# 17-INTERFACE.net
KiCad netlist of a schematic drawn in Altium Designer
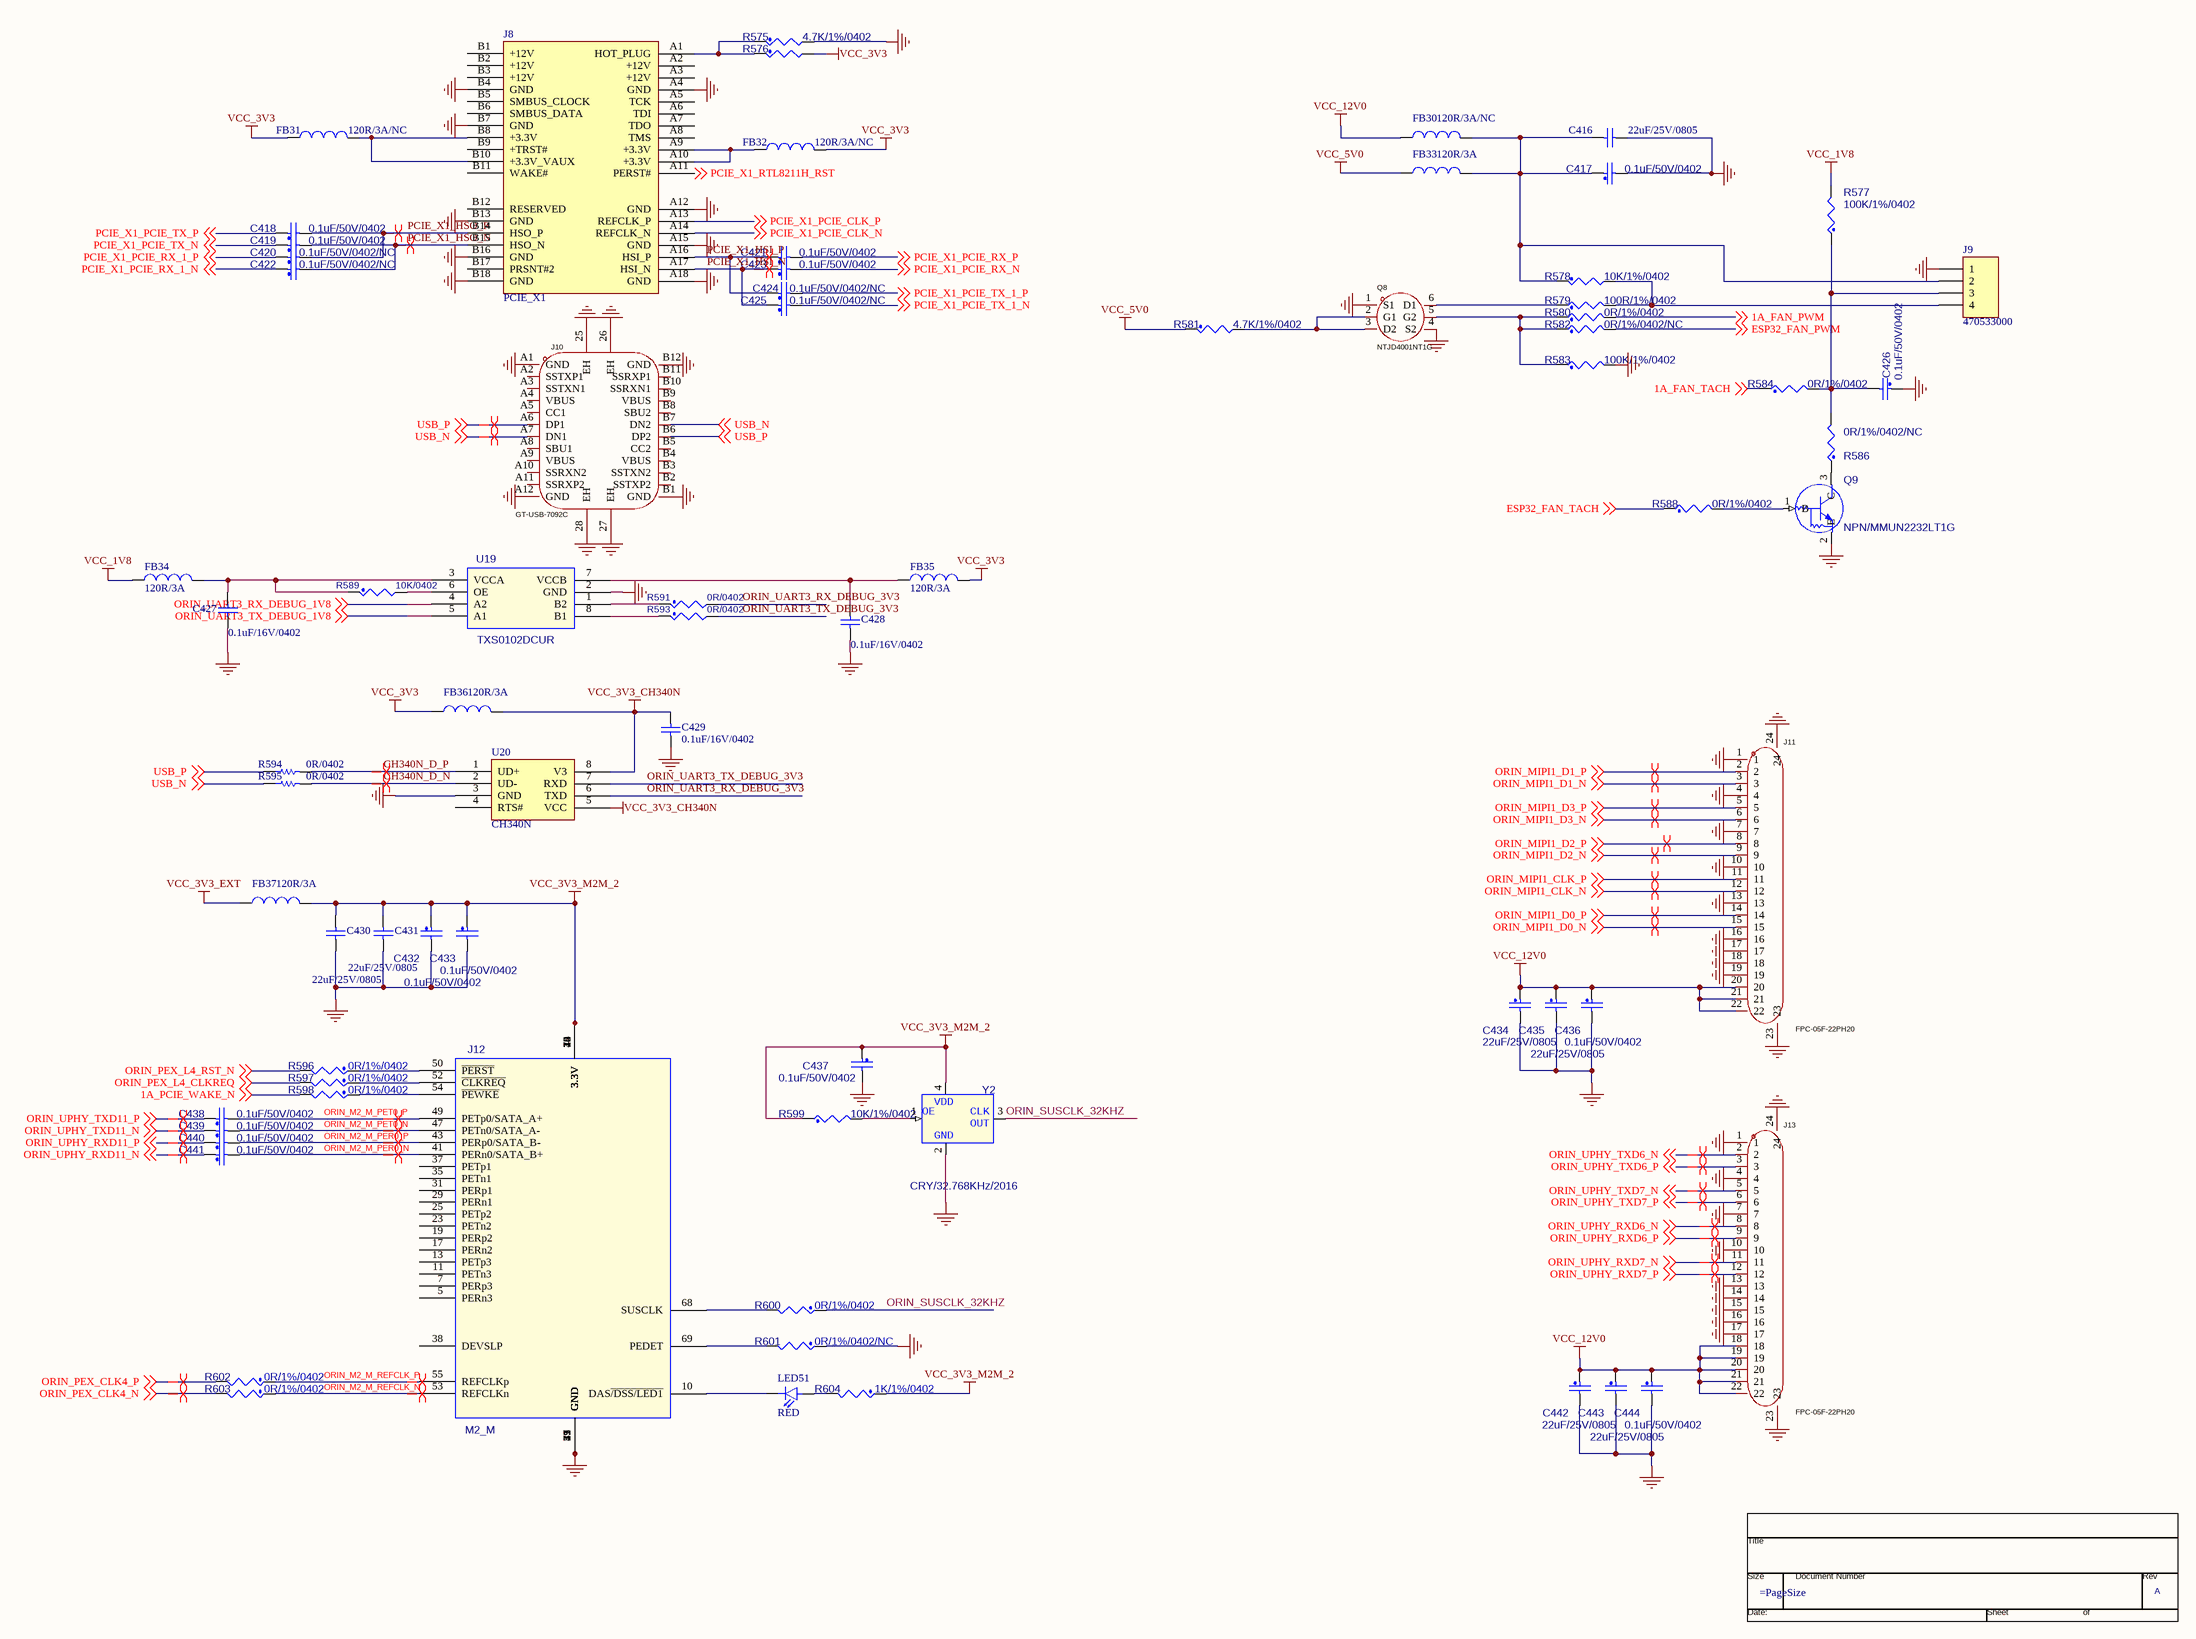
[diagram p0: 17-INTERFACE.SchDoc]

(export (version "E")
  (design (tool "Eeschema 10.0.6"))
  (components
    (comp (ref "C416")
      (value "22uF/25V/0805")
      (description "Capacitor")
      (fields (field (name "PUBLISHER") "Altium Limited"))
      (libsource (lib "LIBS") (part "CAP"))
    )
    (comp (ref "C417")
      (value "0.1uF/50V/0402")
      (footprint "C0402")
      (description "GCM155R71H104KE02/MURATA")
      (fields (field (name "TOLERANCE") "10%") (field (name "VOLTAGE") "16V"))
      (libsource (lib "*") (part "CAP_NP"))
    )
    (comp (ref "C418")
      (value "0.1uF/50V/0402")
      (footprint "C0402")
      (description "GCM155R71H104KE02/MURATA")
      (fields (field (name "TOLERANCE") "10%") (field (name "VOLTAGE") "16V"))
      (libsource (lib "*") (part "CAP_NP"))
    )
    (comp (ref "C419")
      (value "0.1uF/50V/0402")
      (footprint "C0402")
      (description "GCM155R71H104KE02/MURATA")
      (fields (field (name "TOLERANCE") "10%") (field (name "VOLTAGE") "16V"))
      (libsource (lib "*") (part "CAP_NP"))
    )
    (comp (ref "C420")
      (value "0.1uF/50V/0402/NC")
      (footprint "C0402")
      (description "GCM155R71H104KE02/MURATA")
      (fields (field (name "TOLERANCE") "10%") (field (name "VOLTAGE") "16V"))
      (libsource (lib "*") (part "CAP_NP"))
    )
    (comp (ref "C421")
      (value "0.1uF/50V/0402")
      (footprint "C0402")
      (description "GCM155R71H104KE02/MURATA")
      (fields (field (name "TOLERANCE") "10%") (field (name "VOLTAGE") "16V"))
      (libsource (lib "*") (part "CAP_NP"))
    )
    (comp (ref "C422")
      (value "0.1uF/50V/0402/NC")
      (footprint "C0402")
      (description "GCM155R71H104KE02/MURATA")
      (fields (field (name "TOLERANCE") "10%") (field (name "VOLTAGE") "16V"))
      (libsource (lib "*") (part "CAP_NP"))
    )
    (comp (ref "C423")
      (value "0.1uF/50V/0402")
      (footprint "C0402")
      (description "GCM155R71H104KE02/MURATA")
      (fields (field (name "TOLERANCE") "10%") (field (name "VOLTAGE") "16V"))
      (libsource (lib "*") (part "CAP_NP"))
    )
    (comp (ref "C424")
      (value "0.1uF/50V/0402/NC")
      (footprint "C0402")
      (description "GCM155R71H104KE02/MURATA")
      (fields (field (name "TOLERANCE") "10%") (field (name "VOLTAGE") "16V"))
      (libsource (lib "*") (part "CAP_NP"))
    )
    (comp (ref "C425")
      (value "0.1uF/50V/0402/NC")
      (footprint "C0402")
      (description "GCM155R71H104KE02/MURATA")
      (fields (field (name "TOLERANCE") "10%") (field (name "VOLTAGE") "16V"))
      (libsource (lib "*") (part "CAP_NP"))
    )
    (comp (ref "C426")
      (value "0.1uF/50V/0402")
      (footprint "C0402")
      (description "GCM155R71H104KE02/MURATA")
      (fields (field (name "TOLERANCE") "10%") (field (name "VOLTAGE") "16V"))
      (libsource (lib "*") (part "CAP_NP"))
    )
    (comp (ref "C427")
      (value "0.1uF/16V/0402")
      (description "Capacitor")
      (fields (field (name "PUBLISHER") "Altium Limited"))
      (libsource (lib "LIBS") (part "CAP"))
    )
    (comp (ref "C428")
      (value "0.1uF/16V/0402")
      (description "Capacitor")
      (fields (field (name "PUBLISHER") "Altium Limited"))
      (libsource (lib "LIBS") (part "CAP"))
    )
    (comp (ref "C429")
      (value "0.1uF/16V/0402")
      (description "Capacitor")
      (fields (field (name "PUBLISHER") "Altium Limited"))
      (libsource (lib "LIBS") (part "CAP"))
    )
    (comp (ref "C430")
      (value "22uF/25V/0805")
      (description "Capacitor")
      (fields (field (name "PUBLISHER") "Altium Limited"))
      (libsource (lib "LIBS") (part "CAP"))
    )
    (comp (ref "C431")
      (value "22uF/25V/0805")
      (description "Capacitor")
      (fields (field (name "PUBLISHER") "Altium Limited"))
      (libsource (lib "LIBS") (part "CAP"))
    )
    (comp (ref "C432")
      (value "0.1uF/50V/0402")
      (footprint "C0402")
      (description "GCM155R71H104KE02/MURATA")
      (fields (field (name "TOLERANCE") "10%") (field (name "VOLTAGE") "16V"))
      (libsource (lib "*") (part "CAP_NP"))
    )
    (comp (ref "C433")
      (value "0.1uF/50V/0402")
      (footprint "C0402")
      (description "GCM155R71H104KE02/MURATA")
      (fields (field (name "TOLERANCE") "10%") (field (name "VOLTAGE") "16V"))
      (libsource (lib "*") (part "CAP_NP"))
    )
    (comp (ref "C434")
      (value "22uF/25V/0805")
      (footprint "C0805")
      (description "GRT31CC71E226ME13/MURATA")
      (fields (field (name "VOLTAGE") "10v") (field (name "TOLERANCE") "10%"))
      (libsource (lib "*") (part "CAP_NP"))
    )
    (comp (ref "C435")
      (value "22uF/25V/0805")
      (footprint "C0805")
      (description "GRT31CC71E226ME13/MURATA")
      (fields (field (name "VOLTAGE") "10v") (field (name "TOLERANCE") "10%"))
      (libsource (lib "*") (part "CAP_NP"))
    )
    (comp (ref "C436")
      (value "0.1uF/50V/0402")
      (footprint "C0402")
      (description "GCM155R71H104KE02/MURATA")
      (fields (field (name "TOLERANCE") "10%") (field (name "VOLTAGE") "16V"))
      (libsource (lib "*") (part "CAP_NP"))
    )
    (comp (ref "C437")
      (value "0.1uF/50V/0402")
      (footprint "C0402")
      (description "GCM155R71H104KE02/MURATA")
      (libsource (lib "*") (part "CAP_NP_Dup1"))
    )
    (comp (ref "C438")
      (value "0.1uF/50V/0402")
      (footprint "C0402")
      (description "GCM155R71H104KE02/MURATA")
      (fields (field (name "TOLERANCE") "10%") (field (name "VOLTAGE") "16V"))
      (libsource (lib "*") (part "CAP_NP"))
    )
    (comp (ref "C439")
      (value "0.1uF/50V/0402")
      (footprint "C0402")
      (description "GCM155R71H104KE02/MURATA")
      (fields (field (name "TOLERANCE") "10%") (field (name "VOLTAGE") "16V"))
      (libsource (lib "*") (part "CAP_NP"))
    )
    (comp (ref "C440")
      (value "0.1uF/50V/0402")
      (footprint "C0402")
      (description "GCM155R71H104KE02/MURATA")
      (fields (field (name "TOLERANCE") "10%") (field (name "VOLTAGE") "16V"))
      (libsource (lib "*") (part "CAP_NP"))
    )
    (comp (ref "C441")
      (value "0.1uF/50V/0402")
      (footprint "C0402")
      (description "GCM155R71H104KE02/MURATA")
      (fields (field (name "TOLERANCE") "10%") (field (name "VOLTAGE") "16V"))
      (libsource (lib "*") (part "CAP_NP"))
    )
    (comp (ref "C442")
      (value "22uF/25V/0805")
      (footprint "C0805")
      (description "GRT31CC71E226ME13/MURATA")
      (fields (field (name "VOLTAGE") "10v") (field (name "TOLERANCE") "10%"))
      (libsource (lib "*") (part "CAP_NP"))
    )
    (comp (ref "C443")
      (value "22uF/25V/0805")
      (footprint "C0805")
      (description "GRT31CC71E226ME13/MURATA")
      (fields (field (name "VOLTAGE") "10v") (field (name "TOLERANCE") "10%"))
      (libsource (lib "*") (part "CAP_NP"))
    )
    (comp (ref "C444")
      (value "0.1uF/50V/0402")
      (footprint "C0402")
      (description "GCM155R71H104KE02/MURATA")
      (fields (field (name "TOLERANCE") "10%") (field (name "VOLTAGE") "16V"))
      (libsource (lib "*") (part "CAP_NP"))
    )
    (comp (ref "FB30")
      (value "120R/3A/NC")
      (footprint "L0603")
      (description "BLM18KG121TN1D")
      (fields (field (name "PUBLISHER") "Altium Limited"))
      (libsource (lib "LIBS") (part "Inductor"))
    )
    (comp (ref "FB31")
      (value "120R/3A/NC")
      (footprint "L0603")
      (description "BLM18KG121TN1D")
      (fields (field (name "PUBLISHER") "Altium Limited"))
      (libsource (lib "LIBS") (part "Inductor"))
    )
    (comp (ref "FB32")
      (value "120R/3A/NC")
      (footprint "L0603")
      (description "BLM18KG121TN1D")
      (fields (field (name "PUBLISHER") "Altium Limited"))
      (libsource (lib "LIBS") (part "Inductor"))
    )
    (comp (ref "FB33")
      (value "120R/3A")
      (footprint "L0603")
      (description "BLM18KG121TN1D")
      (fields (field (name "PUBLISHER") "Altium Limited"))
      (libsource (lib "LIBS") (part "Inductor"))
    )
    (comp (ref "FB34")
      (value "120R/3A")
      (footprint "L0603")
      (description "BLM18KG121TN1D")
      (fields (field (name "PUBLISHER") "Altium Limited"))
      (libsource (lib "LIBS") (part "Inductor"))
    )
    (comp (ref "FB35")
      (value "120R/3A")
      (footprint "L0603")
      (description "BLM18KG121TN1D")
      (fields (field (name "PUBLISHER") "Altium Limited"))
      (libsource (lib "LIBS") (part "Inductor"))
    )
    (comp (ref "FB36")
      (value "120R/3A")
      (footprint "L0603")
      (description "BLM18KG121TN1D")
      (fields (field (name "PUBLISHER") "Altium Limited"))
      (libsource (lib "LIBS") (part "Inductor"))
    )
    (comp (ref "FB37")
      (value "120R/3A")
      (footprint "L0603")
      (description "BLM18KG121TN1D")
      (fields (field (name "PUBLISHER") "Altium Limited"))
      (libsource (lib "LIBS") (part "Inductor"))
    )
    (comp (ref "J8")
      (value "PCIE_X1")
      (footprint "PCIeX16-GF-2D-1000-1K-O36")
      (libsource (lib "LIBS") (part "PCIE_X1"))
    )
    (comp (ref "J9")
      (value "470533000")
      (footprint "470533000")
      (description "Header, 4-Pin")
      (fields (field (name "PUBLISHER") "Altium Limited"))
      (libsource (lib "LIBS") (part "Header 4"))
    )
    (comp (ref "J10")
      (value "GT-USB-7092C")
      (footprint "USB-C-SMD_GT-USB-7092C")
      (fields (field (name "MANUFACTURER") "G-Switch(品赞)"))
      (libsource (lib "altium-import") (part "root_0_GT-USB-7092C_"))
    )
    (comp (ref "J11")
      (value "FPC-05F-22PH20")
      (footprint "FPC-SMD_22P-P0.50_FPC-05F-22PH20")
      (fields (field (name "MANUFACTURER") "XUNPU(讯普)"))
      (libsource (lib "altium-import") (part "root_0_FPC-05F-22PH20_"))
    )
    (comp (ref "J12")
      (value "M2_M")
      (footprint "PCIe_M.2_Connectors_P=0.5mm_H=4.2mm_KeyM - 1")
      (libsource (lib "LIBS") (part "M2_M"))
    )
    (comp (ref "J13")
      (value "FPC-05F-22PH20")
      (footprint "FPC-SMD_22P-P0.50_FPC-05F-22PH20")
      (fields (field (name "MANUFACTURER") "XUNPU(讯普)"))
      (libsource (lib "altium-import") (part "root_0_FPC-05F-22PH20_"))
    )
    (comp (ref "LED51") (value "RED") (footprint "LED0603") (libsource (lib "LIBS") (part "LED")))
    (comp (ref "Q8")
      (value "NTJD4001NT1G")
      (footprint "SOT-363_L2.0-W1.3-P0.65-LS2.1-TL")
      (fields (field (name "MANUFACTURER") "onsemi(安森美)"))
      (libsource (lib "altium-import") (part "root_0_NTJD4001NT1G_"))
    )
    (comp (ref "Q9")
      (value "NPN/MMUN2232LT1G")
      (footprint "SOT-23")
      (description "MMUN2232LT1G/ONSEMI")
      (libsource (lib "*") (part "DTC143ZE"))
    )
    (comp (ref "R575")
      (value "4.7K/1%/0402")
      (footprint "R0402")
      (description "AC0402FR-074K7L/YAGEO")
      (fields (field (name "TOLERANCE") "5%") (field (name "Comment") "RES_Dup2"))
      (libsource (lib "*") (part "RES_Dup2"))
    )
    (comp (ref "R576")
      (value "RES_Dup2")
      (footprint "R0402")
      (description "AC0402FR-074K7L/YAGEO")
      (fields (field (name "TOLERANCE") "5%"))
      (libsource (lib "*") (part "RES_Dup2"))
    )
    (comp (ref "R577")
      (value "100K/1%/0402")
      (footprint "R0402")
      (description "AC0402FR-070RL/YAGEO")
      (fields (field (name "TOLERANCE") "1%") (field (name "Comment") "RES_Dup2"))
      (libsource (lib "*") (part "RES_Dup2"))
    )
    (comp (ref "R578")
      (value "10K/1%/0402")
      (footprint "R0402")
      (description "AC0402FR-074K7L/YAGEO")
      (fields (field (name "TOLERANCE") "5%") (field (name "Comment") "RES_Dup2"))
      (libsource (lib "*") (part "RES_Dup2"))
    )
    (comp (ref "R579")
      (value "100R/1%/0402")
      (footprint "R0402")
      (description "AC0402FR-070RL/YAGEO")
      (fields (field (name "TOLERANCE") "1%") (field (name "Comment") "RES_Dup2"))
      (libsource (lib "*") (part "RES_Dup2"))
    )
    (comp (ref "R580")
      (value "0R/1%/0402")
      (footprint "R0402")
      (description "AC0402FR-070RL/YAGEO")
      (fields (field (name "TOLERANCE") "1%") (field (name "Comment") "RES_Dup2"))
      (libsource (lib "*") (part "RES_Dup2"))
    )
    (comp (ref "R581")
      (value "4.7K/1%/0402")
      (footprint "R0402")
      (description "AC0402FR-074K7L/YAGEO")
      (fields (field (name "TOLERANCE") "5%") (field (name "Comment") "RES_Dup2"))
      (libsource (lib "*") (part "RES_Dup2"))
    )
    (comp (ref "R582")
      (value "0R/1%/0402/NC")
      (footprint "R0402")
      (description "AC0402FR-070RL/YAGEO")
      (fields (field (name "TOLERANCE") "1%") (field (name "Comment") "RES_Dup2"))
      (libsource (lib "*") (part "RES_Dup2"))
    )
    (comp (ref "R583")
      (value "100K/1%/0402")
      (footprint "R0402")
      (description "AC0402FR-070RL/YAGEO")
      (fields (field (name "TOLERANCE") "1%") (field (name "Comment") "RES_Dup2"))
      (libsource (lib "*") (part "RES_Dup2"))
    )
    (comp (ref "R584")
      (value "0R/1%/0402")
      (footprint "R0402")
      (description "AC0402FR-070RL/YAGEO")
      (fields (field (name "TOLERANCE") "1%") (field (name "Comment") "RES_Dup2"))
      (libsource (lib "*") (part "RES_Dup2"))
    )
    (comp (ref "R586")
      (value "0R/1%/0402/NC")
      (footprint "R0402")
      (description "AC0402FR-070RL/YAGEO")
      (fields (field (name "TOLERANCE") "1%") (field (name "Comment") "RES_Dup2"))
      (libsource (lib "*") (part "RES_Dup2"))
    )
    (comp (ref "R588")
      (value "0R/1%/0402")
      (footprint "R0402")
      (description "AC0402FR-070RL/YAGEO")
      (fields (field (name "TOLERANCE") "1%") (field (name "Comment") "RES_Dup2"))
      (libsource (lib "*") (part "RES_Dup2"))
    )
    (comp (ref "R589")
      (value "10K/0402")
      (footprint "R0402")
      (description "RES MF 1.0K 1/16W 5% 0402")
      (fields (field (name "TOLERANCE") "5%"))
      (libsource (lib "*") (part "RES_Dup1"))
    )
    (comp (ref "R591")
      (value "0R/0402")
      (footprint "R0402")
      (description "RES MF 1.0K 1/16W 5% 0402")
      (fields (field (name "TOLERANCE") "5%"))
      (libsource (lib "*") (part "RES_Dup1"))
    )
    (comp (ref "R593")
      (value "0R/0402")
      (footprint "R0402")
      (description "RES MF 1.0K 1/16W 5% 0402")
      (fields (field (name "TOLERANCE") "5%"))
      (libsource (lib "*") (part "RES_Dup1"))
    )
    (comp (ref "R594")
      (value "0R/0402")
      (footprint "R0402")
      (description "Semiconductor Resistor")
      (fields (field (name "PUBLISHER") "Altium Limited"))
      (libsource (lib "LIBS") (part "Res Semi"))
    )
    (comp (ref "R595")
      (value "0R/0402")
      (footprint "R0402")
      (description "Semiconductor Resistor")
      (fields (field (name "PUBLISHER") "Altium Limited"))
      (libsource (lib "LIBS") (part "Res Semi"))
    )
    (comp (ref "R596")
      (value "0R/1%/0402")
      (footprint "R0402")
      (description "AC0402FR-070RL/YAGEO")
      (fields (field (name "TOLERANCE") "1%") (field (name "Comment") "RES_Dup2"))
      (libsource (lib "*") (part "RES_Dup2"))
    )
    (comp (ref "R597")
      (value "0R/1%/0402")
      (footprint "R0402")
      (description "AC0402FR-070RL/YAGEO")
      (fields (field (name "TOLERANCE") "1%") (field (name "Comment") "RES_Dup2"))
      (libsource (lib "*") (part "RES_Dup2"))
    )
    (comp (ref "R598")
      (value "0R/1%/0402")
      (footprint "R0402")
      (description "AC0402FR-070RL/YAGEO")
      (fields (field (name "TOLERANCE") "1%") (field (name "Comment") "RES_Dup2"))
      (libsource (lib "*") (part "RES_Dup2"))
    )
    (comp (ref "R599")
      (value "10K/1%/0402")
      (footprint "R0402")
      (description "AC0402FR-0710KL/YAGEO")
      (libsource (lib "*") (part "RES_0"))
    )
    (comp (ref "R600")
      (value "0R/1%/0402")
      (footprint "R0402")
      (description "AC0402FR-070RL/YAGEO")
      (fields (field (name "TOLERANCE") "1%") (field (name "Comment") "RES_Dup2"))
      (libsource (lib "*") (part "RES_Dup2"))
    )
    (comp (ref "R601")
      (value "0R/1%/0402/NC")
      (footprint "R0402")
      (description "AC0402FR-070RL/YAGEO")
      (fields (field (name "TOLERANCE") "1%") (field (name "Comment") "RES_Dup2"))
      (libsource (lib "*") (part "RES_Dup2"))
    )
    (comp (ref "R602")
      (value "0R/1%/0402")
      (footprint "R0402")
      (description "AC0402FR-070RL/YAGEO")
      (fields (field (name "TOLERANCE") "1%") (field (name "Comment") "RES_Dup2"))
      (libsource (lib "*") (part "RES_Dup2"))
    )
    (comp (ref "R603")
      (value "0R/1%/0402")
      (footprint "R0402")
      (description "AC0402FR-070RL/YAGEO")
      (fields (field (name "TOLERANCE") "1%") (field (name "Comment") "RES_Dup2"))
      (libsource (lib "*") (part "RES_Dup2"))
    )
    (comp (ref "R604")
      (value "1K/1%/0402")
      (footprint "R0402")
      (description "AC0402FR-070RL/YAGEO")
      (fields (field (name "TOLERANCE") "1%") (field (name "Comment") "RES_Dup2"))
      (libsource (lib "*") (part "RES_Dup2"))
    )
    (comp (ref "U19")
      (value "TXS0102DCUR")
      (footprint "VSSOP-8-TXS0102DCUR")
      (description "TXS0102DCUR/TI")
      (libsource (lib "*") (part "TXS0102DCUR"))
    )
    (comp (ref "U20")
      (value "CH340N")
      (footprint "SOP-8_L4.9-W3.9-P1.27-LS6.0-BL")
      (libsource (lib "LIBS") (part "CH340N"))
    )
    (comp (ref "Y2")
      (value "CRY/32.768KHz/2016")
      (footprint "CRY2016")
      (description "SX1M32.768KM10F30TNN/SCTF")
      (libsource (lib "*") (part "CLKGEN-SM"))
    )
  )
  (nets
    (net (code "1") (name "/CH340N_D_N") (class "Default")
      (node (ref "R595") (pin "2") (pinfunction "2_2") (pintype "passive"))
      (node (ref "U20") (pin "2") (pinfunction "UD-_2") (pintype "passive"))
    )
    (net (code "2") (name "/CH340N_D_P") (class "Default")
      (node (ref "R594") (pin "2") (pinfunction "2_2") (pintype "passive"))
      (node (ref "U20") (pin "1") (pinfunction "UD+_1") (pintype "passive"))
    )
    (net (code "3") (name "/ORIN_M2_M_PER0_N") (class "Default")
      (node (ref "C441") (pin "2") (pinfunction "2_2") (pintype "passive"))
      (node (ref "J12") (pin "41") (pinfunction "PERn0/SATA_B+_41") (pintype "passive"))
    )
    (net (code "4") (name "/ORIN_M2_M_PER0_P") (class "Default")
      (node (ref "C440") (pin "2") (pinfunction "2_2") (pintype "passive"))
      (node (ref "J12") (pin "43") (pinfunction "PERp0/SATA_B-_43") (pintype "passive"))
    )
    (net (code "5") (name "/ORIN_M2_M_PET0_N") (class "Default")
      (node (ref "C439") (pin "2") (pinfunction "2_2") (pintype "passive"))
      (node (ref "J12") (pin "47") (pinfunction "PETn0/SATA_A-_47") (pintype "passive"))
    )
    (net (code "6") (name "/ORIN_M2_M_PET0_P") (class "Default")
      (node (ref "C438") (pin "2") (pinfunction "2_2") (pintype "passive"))
      (node (ref "J12") (pin "49") (pinfunction "PETp0/SATA_A+_49") (pintype "passive"))
    )
    (net (code "7") (name "/ORIN_M2_M_REFCLK_N") (class "Default")
      (node (ref "J12") (pin "53") (pinfunction "REFCLKn_53") (pintype "passive"))
      (node (ref "R603") (pin "1") (pinfunction "1_1") (pintype "passive"))
    )
    (net (code "8") (name "/ORIN_M2_M_REFCLK_P") (class "Default")
      (node (ref "J12") (pin "55") (pinfunction "REFCLKp_55") (pintype "passive"))
      (node (ref "R602") (pin "1") (pinfunction "1_1") (pintype "passive"))
    )
    (net (code "9") (name "/ORIN_SUSCLK_32KHZ") (class "Default")
      (node (ref "R600") (pin "1") (pinfunction "1_1") (pintype "passive"))
      (node (ref "Y2") (pin "3") (pinfunction "CLKOUT_3") (pintype "tri_state"))
    )
    (net (code "10") (name "/ORIN_UART3_RX_DEBUG_3V3") (class "Default")
      (node (ref "R591") (pin "2") (pinfunction "2_2") (pintype "passive"))
      (node (ref "U20") (pin "6") (pinfunction "TXD_6") (pintype "passive"))
    )
    (net (code "11") (name "/ORIN_UART3_TX_DEBUG_3V3") (class "Default")
      (node (ref "R593") (pin "2") (pinfunction "2_2") (pintype "passive"))
      (node (ref "U20") (pin "7") (pinfunction "RXD_7") (pintype "passive"))
    )
    (net (code "12") (name "/PCIE_X1_HSI_N") (class "Default")
      (node (ref "C423") (pin "1") (pinfunction "1_1") (pintype "passive"))
      (node (ref "C425") (pin "1") (pinfunction "1_1") (pintype "passive"))
      (node (ref "J8") (pin "A17") (pinfunction "HSI_N_A17") (pintype "passive"))
    )
    (net (code "13") (name "/PCIE_X1_HSI_P") (class "Default")
      (node (ref "C421") (pin "1") (pinfunction "1_1") (pintype "passive"))
      (node (ref "C424") (pin "1") (pinfunction "1_1") (pintype "passive"))
      (node (ref "J8") (pin "A16") (pinfunction "HSI_P_A16") (pintype "passive"))
    )
    (net (code "14") (name "/PCIE_X1_HSO_N") (class "Default")
      (node (ref "C419") (pin "2") (pinfunction "2_2") (pintype "passive"))
      (node (ref "C422") (pin "2") (pinfunction "2_2") (pintype "passive"))
      (node (ref "J8") (pin "B15") (pinfunction "HSO_N_B15") (pintype "passive"))
    )
    (net (code "15") (name "/PCIE_X1_HSO_P") (class "Default")
      (node (ref "C418") (pin "2") (pinfunction "2_2") (pintype "passive"))
      (node (ref "C420") (pin "2") (pinfunction "2_2") (pintype "passive"))
      (node (ref "J8") (pin "B14") (pinfunction "HSO_P_B14") (pintype "passive"))
    )
    (net (code "16") (name "1A_FAN_PWM") (class "Default")
      (node (ref "R580") (pin "2") (pinfunction "2_2") (pintype "passive"))
    )
    (net (code "17") (name "1A_FAN_TACH") (class "Default")
      (node (ref "R584") (pin "1") (pinfunction "1_1") (pintype "passive"))
    )
    (net (code "18") (name "1A_PCIE_WAKE_N") (class "Default")
      (node (ref "R598") (pin "2") (pinfunction "2_2") (pintype "passive"))
    )
    (net (code "19") (name "ESP32_FAN_PWM") (class "Default")
      (node (ref "R582") (pin "2") (pinfunction "2_2") (pintype "passive"))
    )
    (net (code "20") (name "ESP32_FAN_TACH") (class "Default")
      (node (ref "R588") (pin "1") (pinfunction "1_1") (pintype "passive"))
    )
    (net (code "21") (name "GND") (class "Default")
      (node (ref "C416") (pin "1") (pinfunction "1_1") (pintype "passive"))
      (node (ref "C417") (pin "2") (pinfunction "2_2") (pintype "passive"))
      (node (ref "C426") (pin "1") (pinfunction "1_1") (pintype "passive"))
      (node (ref "C427") (pin "1") (pinfunction "1_1") (pintype "passive"))
      (node (ref "C428") (pin "1") (pinfunction "1_1") (pintype "passive"))
      (node (ref "C429") (pin "1") (pinfunction "1_1") (pintype "passive"))
      (node (ref "C430") (pin "1") (pinfunction "1_1") (pintype "passive"))
      (node (ref "C431") (pin "1") (pinfunction "1_1") (pintype "passive"))
      (node (ref "C432") (pin "2") (pinfunction "2_2") (pintype "passive"))
      (node (ref "C433") (pin "2") (pinfunction "2_2") (pintype "passive"))
      (node (ref "C434") (pin "2") (pinfunction "2_2") (pintype "passive"))
      (node (ref "C435") (pin "2") (pinfunction "2_2") (pintype "passive"))
      (node (ref "C436") (pin "2") (pinfunction "2_2") (pintype "passive"))
      (node (ref "C437") (pin "2") (pinfunction "2_2") (pintype "passive"))
      (node (ref "C442") (pin "2") (pinfunction "2_2") (pintype "passive"))
      (node (ref "C443") (pin "2") (pinfunction "2_2") (pintype "passive"))
      (node (ref "C444") (pin "2") (pinfunction "2_2") (pintype "passive"))
      (node (ref "J10") (pin "25") (pinfunction "EH_25") (pintype "passive"))
      (node (ref "J10") (pin "26") (pinfunction "EH_26") (pintype "passive"))
      (node (ref "J10") (pin "27") (pinfunction "EH_27") (pintype "passive"))
      (node (ref "J10") (pin "28") (pinfunction "EH_28") (pintype "passive"))
      (node (ref "J10") (pin "A1") (pinfunction "GND_A1") (pintype "passive"))
      (node (ref "J10") (pin "A12") (pinfunction "GND_A12") (pintype "passive"))
      (node (ref "J10") (pin "B1") (pinfunction "GND_B1") (pintype "passive"))
      (node (ref "J10") (pin "B12") (pinfunction "GND_B12") (pintype "passive"))
      (node (ref "J11") (pin "1") (pinfunction "1_1") (pintype "passive"))
      (node (ref "J11") (pin "10") (pinfunction "10_10") (pintype "passive"))
      (node (ref "J11") (pin "13") (pinfunction "13_13") (pintype "passive"))
      (node (ref "J11") (pin "16") (pinfunction "16_16") (pintype "passive"))
      (node (ref "J11") (pin "17") (pinfunction "17_17") (pintype "passive"))
      (node (ref "J11") (pin "18") (pinfunction "18_18") (pintype "passive"))
      (node (ref "J11") (pin "19") (pinfunction "19_19") (pintype "passive"))
      (node (ref "J11") (pin "23") (pinfunction "23_23") (pintype "passive"))
      (node (ref "J11") (pin "24") (pinfunction "24_24") (pintype "passive"))
      (node (ref "J11") (pin "4") (pinfunction "4_4") (pintype "passive"))
      (node (ref "J11") (pin "7") (pinfunction "7_7") (pintype "passive"))
      (node (ref "J12") (pin "1") (pinfunction "GND_1") (pintype "passive"))
      (node (ref "J12") (pin "15") (pinfunction "GND_15") (pintype "passive"))
      (node (ref "J12") (pin "21") (pinfunction "GND_21") (pintype "passive"))
      (node (ref "J12") (pin "27") (pinfunction "GND_27") (pintype "passive"))
      (node (ref "J12") (pin "3") (pinfunction "GND_3") (pintype "passive"))
      (node (ref "J12") (pin "33") (pinfunction "GND_33") (pintype "passive"))
      (node (ref "J12") (pin "39") (pinfunction "GND_39") (pintype "passive"))
      (node (ref "J12") (pin "45") (pinfunction "GND_45") (pintype "passive"))
      (node (ref "J12") (pin "51") (pinfunction "GND_51") (pintype "passive"))
      (node (ref "J12") (pin "57") (pinfunction "GND_57") (pintype "passive"))
      (node (ref "J12") (pin "71") (pinfunction "GND_71") (pintype "passive"))
      (node (ref "J12") (pin "73") (pinfunction "GND_73") (pintype "passive"))
      (node (ref "J12") (pin "75") (pinfunction "GND_75") (pintype "passive"))
      (node (ref "J12") (pin "9") (pinfunction "GND_9") (pintype "passive"))
      (node (ref "J13") (pin "1") (pinfunction "1_1") (pintype "passive"))
      (node (ref "J13") (pin "10") (pinfunction "10_10") (pintype "passive"))
      (node (ref "J13") (pin "13") (pinfunction "13_13") (pintype "passive"))
      (node (ref "J13") (pin "14") (pinfunction "14_14") (pintype "passive"))
      (node (ref "J13") (pin "15") (pinfunction "15_15") (pintype "passive"))
      (node (ref "J13") (pin "16") (pinfunction "16_16") (pintype "passive"))
      (node (ref "J13") (pin "17") (pinfunction "17_17") (pintype "passive"))
      (node (ref "J13") (pin "23") (pinfunction "23_23") (pintype "passive"))
      (node (ref "J13") (pin "24") (pinfunction "24_24") (pintype "passive"))
      (node (ref "J13") (pin "4") (pinfunction "4_4") (pintype "passive"))
      (node (ref "J13") (pin "7") (pinfunction "7_7") (pintype "passive"))
      (node (ref "J8") (pin "A12") (pinfunction "GND_A12") (pintype "passive"))
      (node (ref "J8") (pin "A15") (pinfunction "GND_A15") (pintype "passive"))
      (node (ref "J8") (pin "A18") (pinfunction "GND_A18") (pintype "passive"))
      (node (ref "J8") (pin "A4") (pinfunction "GND_A4") (pintype "passive"))
      (node (ref "J8") (pin "B13") (pinfunction "GND_B13") (pintype "passive"))
      (node (ref "J8") (pin "B16") (pinfunction "GND_B16") (pintype "passive"))
      (node (ref "J8") (pin "B18") (pinfunction "GND_B18") (pintype "passive"))
      (node (ref "J8") (pin "B4") (pinfunction "GND_B4") (pintype "passive"))
      (node (ref "J8") (pin "B7") (pinfunction "GND_B7") (pintype "passive"))
      (node (ref "J9") (pin "1") (pinfunction "1_1") (pintype "passive"))
      (node (ref "Q8") (pin "1") (pinfunction "S1_1") (pintype "passive"))
      (node (ref "Q8") (pin "4") (pinfunction "S2_4") (pintype "passive"))
      (node (ref "Q9") (pin "2") (pinfunction "E_2") (pintype "passive"))
      (node (ref "R575") (pin "2") (pinfunction "2_2") (pintype "passive"))
      (node (ref "R583") (pin "2") (pinfunction "2_2") (pintype "passive"))
      (node (ref "R601") (pin "1") (pinfunction "1_1") (pintype "passive"))
      (node (ref "U19") (pin "2") (pinfunction "GND_2") (pintype "passive"))
      (node (ref "U20") (pin "3") (pinfunction "GND_3") (pintype "passive"))
      (node (ref "Y2") (pin "2") (pinfunction "GND_2") (pintype "power_in"))
    )
    (net (code "22") (name "Net-(C416-Pad2)") (class "Default")
      (node (ref "C416") (pin "2") (pinfunction "2_2") (pintype "passive"))
      (node (ref "C417") (pin "1") (pinfunction "1_1") (pintype "passive"))
      (node (ref "FB30") (pin "2") (pinfunction "2_2") (pintype "passive"))
      (node (ref "FB33") (pin "2") (pinfunction "2_2") (pintype "passive"))
      (node (ref "J9") (pin "2") (pinfunction "2_2") (pintype "passive"))
      (node (ref "R578") (pin "1") (pinfunction "1_1") (pintype "passive"))
    )
    (net (code "23") (name "Net-(C426-Pad2)") (class "Default")
      (node (ref "C426") (pin "2") (pinfunction "2_2") (pintype "passive"))
      (node (ref "J9") (pin "3") (pinfunction "3_3") (pintype "passive"))
      (node (ref "R577") (pin "1") (pinfunction "1_1") (pintype "passive"))
      (node (ref "R584") (pin "2") (pinfunction "2_2") (pintype "passive"))
      (node (ref "R586") (pin "2") (pinfunction "2_2") (pintype "passive"))
    )
    (net (code "24") (name "Net-(FB32-Pad1)") (class "Default")
      (node (ref "FB32") (pin "1") (pinfunction "1_1") (pintype "passive"))
      (node (ref "J8") (pin "A10") (pinfunction "+3.3V_A10") (pintype "passive"))
      (node (ref "J8") (pin "A9") (pinfunction "+3.3V_A9") (pintype "passive"))
    )
    (net (code "25") (name "Net-(J8-+3.3V_VAUX)") (class "Default")
      (node (ref "FB31") (pin "2") (pinfunction "2_2") (pintype "passive"))
      (node (ref "J8") (pin "B10") (pinfunction "+3.3V_VAUX_B10") (pintype "passive"))
      (node (ref "J8") (pin "B8") (pinfunction "+3.3V_B8") (pintype "passive"))
    )
    (net (code "26") (name "Net-(J8-HOT_PLUG)") (class "Default")
      (node (ref "J8") (pin "A1") (pinfunction "HOT_PLUG_A1") (pintype "passive"))
      (node (ref "R575") (pin "1") (pinfunction "1_1") (pintype "passive"))
      (node (ref "R576") (pin "1") (pinfunction "1_1") (pintype "passive"))
    )
    (net (code "27") (name "Net-(J9-Pad4)") (class "Default")
      (node (ref "J9") (pin "4") (pinfunction "4_4") (pintype "passive"))
      (node (ref "R578") (pin "2") (pinfunction "2_2") (pintype "passive"))
      (node (ref "R579") (pin "2") (pinfunction "2_2") (pintype "passive"))
    )
    (net (code "28") (name "Net-(J12-DAS~{{slash}DSS{slash}LED1})") (class "Default")
      (node (ref "J12") (pin "10") (pinfunction "DAS~{/DSS/LED1}_10") (pintype "passive"))
      (node (ref "LED51") (pin "2") (pinfunction "2_2") (pintype "passive"))
    )
    (net (code "29") (name "Net-(J12-PEDET)") (class "Default")
      (node (ref "J12") (pin "69") (pinfunction "PEDET_69") (pintype "passive"))
      (node (ref "R601") (pin "2") (pinfunction "2_2") (pintype "passive"))
    )
    (net (code "30") (name "Net-(J12-SUSCLK)") (class "Default")
      (node (ref "J12") (pin "68") (pinfunction "SUSCLK_68") (pintype "passive"))
      (node (ref "R600") (pin "2") (pinfunction "2_2") (pintype "passive"))
    )
    (net (code "31") (name "Net-(J12-~{CLKREQ})") (class "Default")
      (node (ref "J12") (pin "52") (pinfunction "~{CLKREQ}_52") (pintype "passive"))
      (node (ref "R597") (pin "1") (pinfunction "1_1") (pintype "passive"))
    )
    (net (code "32") (name "Net-(J12-~{PERST})") (class "Default")
      (node (ref "J12") (pin "50") (pinfunction "~{PERST}_50") (pintype "passive"))
      (node (ref "R596") (pin "1") (pinfunction "1_1") (pintype "passive"))
    )
    (net (code "33") (name "Net-(J12-~{PEWKE})") (class "Default")
      (node (ref "J12") (pin "54") (pinfunction "~{PEWKE}_54") (pintype "passive"))
      (node (ref "R598") (pin "1") (pinfunction "1_1") (pintype "passive"))
    )
    (net (code "34") (name "Net-(LED51-Pad1)") (class "Default")
      (node (ref "LED51") (pin "1") (pinfunction "1_1") (pintype "passive"))
      (node (ref "R604") (pin "2") (pinfunction "2_2") (pintype "passive"))
    )
    (net (code "35") (name "Net-(Q8-D1)") (class "Default")
      (node (ref "Q8") (pin "6") (pinfunction "D1_6") (pintype "passive"))
      (node (ref "R579") (pin "1") (pinfunction "1_1") (pintype "passive"))
    )
    (net (code "36") (name "Net-(Q8-D2)") (class "Default")
      (node (ref "Q8") (pin "2") (pinfunction "G1_2") (pintype "passive"))
      (node (ref "Q8") (pin "3") (pinfunction "D2_3") (pintype "passive"))
      (node (ref "R581") (pin "2") (pinfunction "2_2") (pintype "passive"))
    )
    (net (code "37") (name "Net-(Q8-G2)") (class "Default")
      (node (ref "Q8") (pin "5") (pinfunction "G2_5") (pintype "passive"))
      (node (ref "R580") (pin "1") (pinfunction "1_1") (pintype "passive"))
      (node (ref "R582") (pin "1") (pinfunction "1_1") (pintype "passive"))
      (node (ref "R583") (pin "1") (pinfunction "1_1") (pintype "passive"))
    )
    (net (code "38") (name "Net-(Q9-B)") (class "Default")
      (node (ref "Q9") (pin "1") (pinfunction "B_1") (pintype "input"))
      (node (ref "R588") (pin "2") (pinfunction "2_2") (pintype "passive"))
    )
    (net (code "39") (name "Net-(Q9-C)") (class "Default")
      (node (ref "Q9") (pin "3") (pinfunction "C_3") (pintype "passive"))
      (node (ref "R586") (pin "1") (pinfunction "1_1") (pintype "passive"))
    )
    (net (code "40") (name "Net-(U19-B1)") (class "Default")
      (node (ref "R593") (pin "1") (pinfunction "1_1") (pintype "passive"))
      (node (ref "U19") (pin "8") (pinfunction "B1_8") (pintype "passive"))
    )
    (net (code "41") (name "Net-(U19-B2)") (class "Default")
      (node (ref "R591") (pin "1") (pinfunction "1_1") (pintype "passive"))
      (node (ref "U19") (pin "1") (pinfunction "B2_1") (pintype "passive"))
    )
    (net (code "42") (name "Net-(U19-OE)") (class "Default")
      (node (ref "R589") (pin "2") (pinfunction "2_2") (pintype "passive"))
      (node (ref "U19") (pin "6") (pinfunction "OE_6") (pintype "passive"))
    )
    (net (code "43") (name "Net-(U19-VCCA)") (class "Default")
      (node (ref "C427") (pin "2") (pinfunction "2_2") (pintype "passive"))
      (node (ref "FB34") (pin "2") (pinfunction "2_2") (pintype "passive"))
      (node (ref "R589") (pin "1") (pinfunction "1_1") (pintype "passive"))
      (node (ref "U19") (pin "3") (pinfunction "VCCA_3") (pintype "passive"))
    )
    (net (code "44") (name "Net-(U19-VCCB)") (class "Default")
      (node (ref "C428") (pin "2") (pinfunction "2_2") (pintype "passive"))
      (node (ref "FB35") (pin "1") (pinfunction "1_1") (pintype "passive"))
      (node (ref "U19") (pin "7") (pinfunction "VCCB_7") (pintype "passive"))
    )
    (net (code "45") (name "Net-(Y2-OE)") (class "Default")
      (node (ref "R599") (pin "2") (pinfunction "2_2") (pintype "passive"))
      (node (ref "Y2") (pin "1") (pinfunction "OE_1") (pintype "input"))
    )
    (net (code "46") (name "ORIN_MIPI1_CLK_N") (class "Default")
      (node (ref "J11") (pin "12") (pinfunction "12_12") (pintype "passive"))
    )
    (net (code "47") (name "ORIN_MIPI1_CLK_P") (class "Default")
      (node (ref "J11") (pin "11") (pinfunction "11_11") (pintype "passive"))
    )
    (net (code "48") (name "ORIN_MIPI1_D0_N") (class "Default")
      (node (ref "J11") (pin "15") (pinfunction "15_15") (pintype "passive"))
    )
    (net (code "49") (name "ORIN_MIPI1_D0_P") (class "Default")
      (node (ref "J11") (pin "14") (pinfunction "14_14") (pintype "passive"))
    )
    (net (code "50") (name "ORIN_MIPI1_D1_N") (class "Default")
      (node (ref "J11") (pin "3") (pinfunction "3_3") (pintype "passive"))
    )
    (net (code "51") (name "ORIN_MIPI1_D1_P") (class "Default")
      (node (ref "J11") (pin "2") (pinfunction "2_2") (pintype "passive"))
    )
    (net (code "52") (name "ORIN_MIPI1_D2_N") (class "Default")
      (node (ref "J11") (pin "9") (pinfunction "9_9") (pintype "passive"))
    )
    (net (code "53") (name "ORIN_MIPI1_D2_P") (class "Default")
      (node (ref "J11") (pin "8") (pinfunction "8_8") (pintype "passive"))
    )
    (net (code "54") (name "ORIN_MIPI1_D3_N") (class "Default")
      (node (ref "J11") (pin "6") (pinfunction "6_6") (pintype "passive"))
    )
    (net (code "55") (name "ORIN_MIPI1_D3_P") (class "Default")
      (node (ref "J11") (pin "5") (pinfunction "5_5") (pintype "passive"))
    )
    (net (code "56") (name "ORIN_PEX_CLK4_N") (class "Default")
      (node (ref "R603") (pin "2") (pinfunction "2_2") (pintype "passive"))
    )
    (net (code "57") (name "ORIN_PEX_CLK4_P") (class "Default")
      (node (ref "R602") (pin "2") (pinfunction "2_2") (pintype "passive"))
    )
    (net (code "58") (name "ORIN_PEX_L4_CLKREQ") (class "Default")
      (node (ref "R597") (pin "2") (pinfunction "2_2") (pintype "passive"))
    )
    (net (code "59") (name "ORIN_PEX_L4_RST_N") (class "Default")
      (node (ref "R596") (pin "2") (pinfunction "2_2") (pintype "passive"))
    )
    (net (code "60") (name "ORIN_UART3_RX_DEBUG_1V8") (class "Default")
      (node (ref "U19") (pin "4") (pinfunction "A2_4") (pintype "passive"))
    )
    (net (code "61") (name "ORIN_UART3_TX_DEBUG_1V8") (class "Default")
      (node (ref "U19") (pin "5") (pinfunction "A1_5") (pintype "passive"))
    )
    (net (code "62") (name "ORIN_UPHY_RXD6_N") (class "Default")
      (node (ref "J13") (pin "8") (pinfunction "8_8") (pintype "passive"))
    )
    (net (code "63") (name "ORIN_UPHY_RXD6_P") (class "Default")
      (node (ref "J13") (pin "9") (pinfunction "9_9") (pintype "passive"))
    )
    (net (code "64") (name "ORIN_UPHY_RXD7_N") (class "Default")
      (node (ref "J13") (pin "11") (pinfunction "11_11") (pintype "passive"))
    )
    (net (code "65") (name "ORIN_UPHY_RXD7_P") (class "Default")
      (node (ref "J13") (pin "12") (pinfunction "12_12") (pintype "passive"))
    )
    (net (code "66") (name "ORIN_UPHY_RXD11_N") (class "Default")
      (node (ref "C441") (pin "1") (pinfunction "1_1") (pintype "passive"))
    )
    (net (code "67") (name "ORIN_UPHY_RXD11_P") (class "Default")
      (node (ref "C440") (pin "1") (pinfunction "1_1") (pintype "passive"))
    )
    (net (code "68") (name "ORIN_UPHY_TXD6_N") (class "Default")
      (node (ref "J13") (pin "2") (pinfunction "2_2") (pintype "passive"))
    )
    (net (code "69") (name "ORIN_UPHY_TXD6_P") (class "Default")
      (node (ref "J13") (pin "3") (pinfunction "3_3") (pintype "passive"))
    )
    (net (code "70") (name "ORIN_UPHY_TXD7_N") (class "Default")
      (node (ref "J13") (pin "5") (pinfunction "5_5") (pintype "passive"))
    )
    (net (code "71") (name "ORIN_UPHY_TXD7_P") (class "Default")
      (node (ref "J13") (pin "6") (pinfunction "6_6") (pintype "passive"))
    )
    (net (code "72") (name "ORIN_UPHY_TXD11_N") (class "Default")
      (node (ref "C439") (pin "1") (pinfunction "1_1") (pintype "passive"))
    )
    (net (code "73") (name "ORIN_UPHY_TXD11_P") (class "Default")
      (node (ref "C438") (pin "1") (pinfunction "1_1") (pintype "passive"))
    )
    (net (code "74") (name "PCIE_X1_PCIE_CLK_N") (class "Default")
      (node (ref "J8") (pin "A14") (pinfunction "REFCLK_N_A14") (pintype "passive"))
    )
    (net (code "75") (name "PCIE_X1_PCIE_CLK_P") (class "Default")
      (node (ref "J8") (pin "A13") (pinfunction "REFCLK_P_A13") (pintype "passive"))
    )
    (net (code "76") (name "PCIE_X1_PCIE_RX_1_N") (class "Default")
      (node (ref "C422") (pin "1") (pinfunction "1_1") (pintype "passive"))
    )
    (net (code "77") (name "PCIE_X1_PCIE_RX_1_P") (class "Default")
      (node (ref "C420") (pin "1") (pinfunction "1_1") (pintype "passive"))
    )
    (net (code "78") (name "PCIE_X1_PCIE_RX_N") (class "Default")
      (node (ref "C423") (pin "2") (pinfunction "2_2") (pintype "passive"))
    )
    (net (code "79") (name "PCIE_X1_PCIE_RX_P") (class "Default")
      (node (ref "C421") (pin "2") (pinfunction "2_2") (pintype "passive"))
    )
    (net (code "80") (name "PCIE_X1_PCIE_TX_1_N") (class "Default")
      (node (ref "C425") (pin "2") (pinfunction "2_2") (pintype "passive"))
    )
    (net (code "81") (name "PCIE_X1_PCIE_TX_1_P") (class "Default")
      (node (ref "C424") (pin "2") (pinfunction "2_2") (pintype "passive"))
    )
    (net (code "82") (name "PCIE_X1_PCIE_TX_N") (class "Default")
      (node (ref "C419") (pin "1") (pinfunction "1_1") (pintype "passive"))
    )
    (net (code "83") (name "PCIE_X1_PCIE_TX_P") (class "Default")
      (node (ref "C418") (pin "1") (pinfunction "1_1") (pintype "passive"))
    )
    (net (code "84") (name "PCIE_X1_RTL8211H_RST") (class "Default")
      (node (ref "J8") (pin "A11") (pinfunction "PERST#_A11") (pintype "passive"))
    )
    (net (code "85") (name "USB_N") (class "Default")
      (node (ref "J10") (pin "A7") (pinfunction "DN1_A7") (pintype "passive"))
      (node (ref "J10") (pin "B7") (pinfunction "DN2_B7") (pintype "passive"))
      (node (ref "R595") (pin "1") (pinfunction "1_1") (pintype "passive"))
    )
    (net (code "86") (name "USB_P") (class "Default")
      (node (ref "J10") (pin "A6") (pinfunction "DP1_A6") (pintype "passive"))
      (node (ref "J10") (pin "B6") (pinfunction "DP2_B6") (pintype "passive"))
      (node (ref "R594") (pin "1") (pinfunction "1_1") (pintype "passive"))
    )
    (net (code "87") (name "VCC_1V8") (class "Default")
      (node (ref "FB34") (pin "1") (pinfunction "1_1") (pintype "passive"))
      (node (ref "R577") (pin "2") (pinfunction "2_2") (pintype "passive"))
    )
    (net (code "88") (name "VCC_3V3") (class "Default")
      (node (ref "FB31") (pin "1") (pinfunction "1_1") (pintype "passive"))
      (node (ref "FB32") (pin "2") (pinfunction "2_2") (pintype "passive"))
      (node (ref "FB35") (pin "2") (pinfunction "2_2") (pintype "passive"))
      (node (ref "FB36") (pin "1") (pinfunction "1_1") (pintype "passive"))
      (node (ref "R576") (pin "2") (pinfunction "2_2") (pintype "passive"))
    )
    (net (code "89") (name "VCC_3V3_CH340N") (class "Default")
      (node (ref "C429") (pin "2") (pinfunction "2_2") (pintype "passive"))
      (node (ref "FB36") (pin "2") (pinfunction "2_2") (pintype "passive"))
      (node (ref "U20") (pin "5") (pinfunction "VCC_5") (pintype "passive"))
      (node (ref "U20") (pin "8") (pinfunction "V3_8") (pintype "passive"))
    )
    (net (code "90") (name "VCC_3V3_EXT") (class "Default")
      (node (ref "FB37") (pin "1") (pinfunction "1_1") (pintype "passive"))
    )
    (net (code "91") (name "VCC_3V3_M2M_2") (class "Default")
      (node (ref "C430") (pin "2") (pinfunction "2_2") (pintype "passive"))
      (node (ref "C431") (pin "2") (pinfunction "2_2") (pintype "passive"))
      (node (ref "C432") (pin "1") (pinfunction "1_1") (pintype "passive"))
      (node (ref "C433") (pin "1") (pinfunction "1_1") (pintype "passive"))
      (node (ref "C437") (pin "1") (pinfunction "1_1") (pintype "passive"))
      (node (ref "FB37") (pin "2") (pinfunction "2_2") (pintype "passive"))
      (node (ref "J12") (pin "12") (pinfunction "3.3V_12") (pintype "passive"))
      (node (ref "J12") (pin "14") (pinfunction "3.3V_14") (pintype "passive"))
      (node (ref "J12") (pin "16") (pinfunction "3.3V_16") (pintype "passive"))
      (node (ref "J12") (pin "18") (pinfunction "3.3V_18") (pintype "passive"))
      (node (ref "J12") (pin "2") (pinfunction "3.3V_2") (pintype "passive"))
      (node (ref "J12") (pin "4") (pinfunction "3.3V_4") (pintype "passive"))
      (node (ref "J12") (pin "70") (pinfunction "3.3V_70") (pintype "passive"))
      (node (ref "J12") (pin "72") (pinfunction "3.3V_72") (pintype "passive"))
      (node (ref "J12") (pin "74") (pinfunction "3.3V_74") (pintype "passive"))
      (node (ref "R599") (pin "1") (pinfunction "1_1") (pintype "passive"))
      (node (ref "R604") (pin "1") (pinfunction "1_1") (pintype "passive"))
      (node (ref "Y2") (pin "4") (pinfunction "VDD_4") (pintype "power_in"))
    )
    (net (code "92") (name "VCC_5V0") (class "Default")
      (node (ref "FB33") (pin "1") (pinfunction "1_1") (pintype "passive"))
      (node (ref "R581") (pin "1") (pinfunction "1_1") (pintype "passive"))
    )
    (net (code "93") (name "VCC_12V0") (class "Default")
      (node (ref "C434") (pin "1") (pinfunction "1_1") (pintype "passive"))
      (node (ref "C435") (pin "1") (pinfunction "1_1") (pintype "passive"))
      (node (ref "C436") (pin "1") (pinfunction "1_1") (pintype "passive"))
      (node (ref "C442") (pin "1") (pinfunction "1_1") (pintype "passive"))
      (node (ref "C443") (pin "1") (pinfunction "1_1") (pintype "passive"))
      (node (ref "C444") (pin "1") (pinfunction "1_1") (pintype "passive"))
      (node (ref "FB30") (pin "1") (pinfunction "1_1") (pintype "passive"))
      (node (ref "J11") (pin "20") (pinfunction "20_20") (pintype "passive"))
      (node (ref "J11") (pin "21") (pinfunction "21_21") (pintype "passive"))
      (node (ref "J11") (pin "22") (pinfunction "22_22") (pintype "passive"))
      (node (ref "J13") (pin "18") (pinfunction "18_18") (pintype "passive"))
      (node (ref "J13") (pin "19") (pinfunction "19_19") (pintype "passive"))
      (node (ref "J13") (pin "20") (pinfunction "20_20") (pintype "passive"))
      (node (ref "J13") (pin "21") (pinfunction "21_21") (pintype "passive"))
      (node (ref "J13") (pin "22") (pinfunction "22_22") (pintype "passive"))
    )
    (net (code "94") (name "unconnected-(J8-+12V-PadA2)") (class "Default")
      (node (ref "J8") (pin "A2") (pinfunction "+12V_A2") (pintype "passive"))
    )
    (net (code "95") (name "unconnected-(J8-+12V-PadA3)") (class "Default")
      (node (ref "J8") (pin "A3") (pinfunction "+12V_A3") (pintype "passive"))
    )
    (net (code "96") (name "unconnected-(J8-+12V-PadB1)") (class "Default")
      (node (ref "J8") (pin "B1") (pinfunction "+12V_B1") (pintype "passive"))
    )
    (net (code "97") (name "unconnected-(J8-+12V-PadB2)") (class "Default")
      (node (ref "J8") (pin "B2") (pinfunction "+12V_B2") (pintype "passive"))
    )
    (net (code "98") (name "unconnected-(J8-+12V-PadB3)") (class "Default")
      (node (ref "J8") (pin "B3") (pinfunction "+12V_B3") (pintype "passive"))
    )
    (net (code "99") (name "unconnected-(J8-+TRST#-PadB9)") (class "Default")
      (node (ref "J8") (pin "B9") (pinfunction "+TRST#_B9") (pintype "passive"))
    )
    (net (code "100") (name "unconnected-(J8-PRSNT#2-PadB17)") (class "Default")
      (node (ref "J8") (pin "B17") (pinfunction "PRSNT#2_B17") (pintype "passive"))
    )
    (net (code "101") (name "unconnected-(J8-RESERVED-PadB12)") (class "Default")
      (node (ref "J8") (pin "B12") (pinfunction "RESERVED_B12") (pintype "passive"))
    )
    (net (code "102") (name "unconnected-(J8-SMBUS_CLOCK-PadB5)") (class "Default")
      (node (ref "J8") (pin "B5") (pinfunction "SMBUS_CLOCK_B5") (pintype "passive"))
    )
    (net (code "103") (name "unconnected-(J8-SMBUS_DATA-PadB6)") (class "Default")
      (node (ref "J8") (pin "B6") (pinfunction "SMBUS_DATA_B6") (pintype "passive"))
    )
    (net (code "104") (name "unconnected-(J8-TCK-PadA5)") (class "Default")
      (node (ref "J8") (pin "A5") (pinfunction "TCK_A5") (pintype "passive"))
    )
    (net (code "105") (name "unconnected-(J8-TDI-PadA6)") (class "Default")
      (node (ref "J8") (pin "A6") (pinfunction "TDI_A6") (pintype "passive"))
    )
    (net (code "106") (name "unconnected-(J8-TDO-PadA7)") (class "Default")
      (node (ref "J8") (pin "A7") (pinfunction "TDO_A7") (pintype "passive"))
    )
    (net (code "107") (name "unconnected-(J8-TMS-PadA8)") (class "Default")
      (node (ref "J8") (pin "A8") (pinfunction "TMS_A8") (pintype "passive"))
    )
    (net (code "108") (name "unconnected-(J8-WAKE#-PadB11)") (class "Default")
      (node (ref "J8") (pin "B11") (pinfunction "WAKE#_B11") (pintype "passive"))
    )
    (net (code "109") (name "unconnected-(J10-CC1-PadA5)") (class "Default")
      (node (ref "J10") (pin "A5") (pinfunction "CC1_A5") (pintype "passive"))
    )
    (net (code "110") (name "unconnected-(J10-CC2-PadB5)") (class "Default")
      (node (ref "J10") (pin "B5") (pinfunction "CC2_B5") (pintype "passive"))
    )
    (net (code "111") (name "unconnected-(J10-SBU1-PadA8)") (class "Default")
      (node (ref "J10") (pin "A8") (pinfunction "SBU1_A8") (pintype "passive"))
    )
    (net (code "112") (name "unconnected-(J10-SBU2-PadB8)") (class "Default")
      (node (ref "J10") (pin "B8") (pinfunction "SBU2_B8") (pintype "passive"))
    )
    (net (code "113") (name "unconnected-(J10-SSRXN1-PadB10)") (class "Default")
      (node (ref "J10") (pin "B10") (pinfunction "SSRXN1_B10") (pintype "passive"))
    )
    (net (code "114") (name "unconnected-(J10-SSRXN2-PadA10)") (class "Default")
      (node (ref "J10") (pin "A10") (pinfunction "SSRXN2_A10") (pintype "passive"))
    )
    (net (code "115") (name "unconnected-(J10-SSRXP1-PadB11)") (class "Default")
      (node (ref "J10") (pin "B11") (pinfunction "SSRXP1_B11") (pintype "passive"))
    )
    (net (code "116") (name "unconnected-(J10-SSRXP2-PadA11)") (class "Default")
      (node (ref "J10") (pin "A11") (pinfunction "SSRXP2_A11") (pintype "passive"))
    )
    (net (code "117") (name "unconnected-(J10-SSTXN1-PadA3)") (class "Default")
      (node (ref "J10") (pin "A3") (pinfunction "SSTXN1_A3") (pintype "passive"))
    )
    (net (code "118") (name "unconnected-(J10-SSTXN2-PadB3)") (class "Default")
      (node (ref "J10") (pin "B3") (pinfunction "SSTXN2_B3") (pintype "passive"))
    )
    (net (code "119") (name "unconnected-(J10-SSTXP1-PadA2)") (class "Default")
      (node (ref "J10") (pin "A2") (pinfunction "SSTXP1_A2") (pintype "passive"))
    )
    (net (code "120") (name "unconnected-(J10-SSTXP2-PadB2)") (class "Default")
      (node (ref "J10") (pin "B2") (pinfunction "SSTXP2_B2") (pintype "passive"))
    )
    (net (code "121") (name "unconnected-(J10-VBUS-PadA4)") (class "Default")
      (node (ref "J10") (pin "A4") (pinfunction "VBUS_A4") (pintype "passive"))
    )
    (net (code "122") (name "unconnected-(J10-VBUS-PadA9)") (class "Default")
      (node (ref "J10") (pin "A9") (pinfunction "VBUS_A9") (pintype "passive"))
    )
    (net (code "123") (name "unconnected-(J10-VBUS-PadB4)") (class "Default")
      (node (ref "J10") (pin "B4") (pinfunction "VBUS_B4") (pintype "passive"))
    )
    (net (code "124") (name "unconnected-(J10-VBUS-PadB9)") (class "Default")
      (node (ref "J10") (pin "B9") (pinfunction "VBUS_B9") (pintype "passive"))
    )
    (net (code "125") (name "unconnected-(J12-DEVSLP-Pad38)") (class "Default")
      (node (ref "J12") (pin "38") (pinfunction "DEVSLP_38") (pintype "passive"))
    )
    (net (code "126") (name "unconnected-(J12-PERn1-Pad29)") (class "Default")
      (node (ref "J12") (pin "29") (pinfunction "PERn1_29") (pintype "passive"))
    )
    (net (code "127") (name "unconnected-(J12-PERn2-Pad17)") (class "Default")
      (node (ref "J12") (pin "17") (pinfunction "PERn2_17") (pintype "passive"))
    )
    (net (code "128") (name "unconnected-(J12-PERn3-Pad5)") (class "Default")
      (node (ref "J12") (pin "5") (pinfunction "PERn3_5") (pintype "passive"))
    )
    (net (code "129") (name "unconnected-(J12-PERp1-Pad31)") (class "Default")
      (node (ref "J12") (pin "31") (pinfunction "PERp1_31") (pintype "passive"))
    )
    (net (code "130") (name "unconnected-(J12-PERp2-Pad19)") (class "Default")
      (node (ref "J12") (pin "19") (pinfunction "PERp2_19") (pintype "passive"))
    )
    (net (code "131") (name "unconnected-(J12-PERp3-Pad7)") (class "Default")
      (node (ref "J12") (pin "7") (pinfunction "PERp3_7") (pintype "passive"))
    )
    (net (code "132") (name "unconnected-(J12-PETn1-Pad35)") (class "Default")
      (node (ref "J12") (pin "35") (pinfunction "PETn1_35") (pintype "passive"))
    )
    (net (code "133") (name "unconnected-(J12-PETn2-Pad23)") (class "Default")
      (node (ref "J12") (pin "23") (pinfunction "PETn2_23") (pintype "passive"))
    )
    (net (code "134") (name "unconnected-(J12-PETn3-Pad11)") (class "Default")
      (node (ref "J12") (pin "11") (pinfunction "PETn3_11") (pintype "passive"))
    )
    (net (code "135") (name "unconnected-(J12-PETp1-Pad37)") (class "Default")
      (node (ref "J12") (pin "37") (pinfunction "PETp1_37") (pintype "passive"))
    )
    (net (code "136") (name "unconnected-(J12-PETp2-Pad25)") (class "Default")
      (node (ref "J12") (pin "25") (pinfunction "PETp2_25") (pintype "passive"))
    )
    (net (code "137") (name "unconnected-(J12-PETp3-Pad13)") (class "Default")
      (node (ref "J12") (pin "13") (pinfunction "PETp3_13") (pintype "passive"))
    )
    (net (code "138") (name "unconnected-(U20-RTS#-Pad4)") (class "Default")
      (node (ref "U20") (pin "4") (pinfunction "RTS#_4") (pintype "passive"))
    )
  )
)
